# Copy_of_Main.net
KiCad netlist of a schematic drawn in Altium Designer
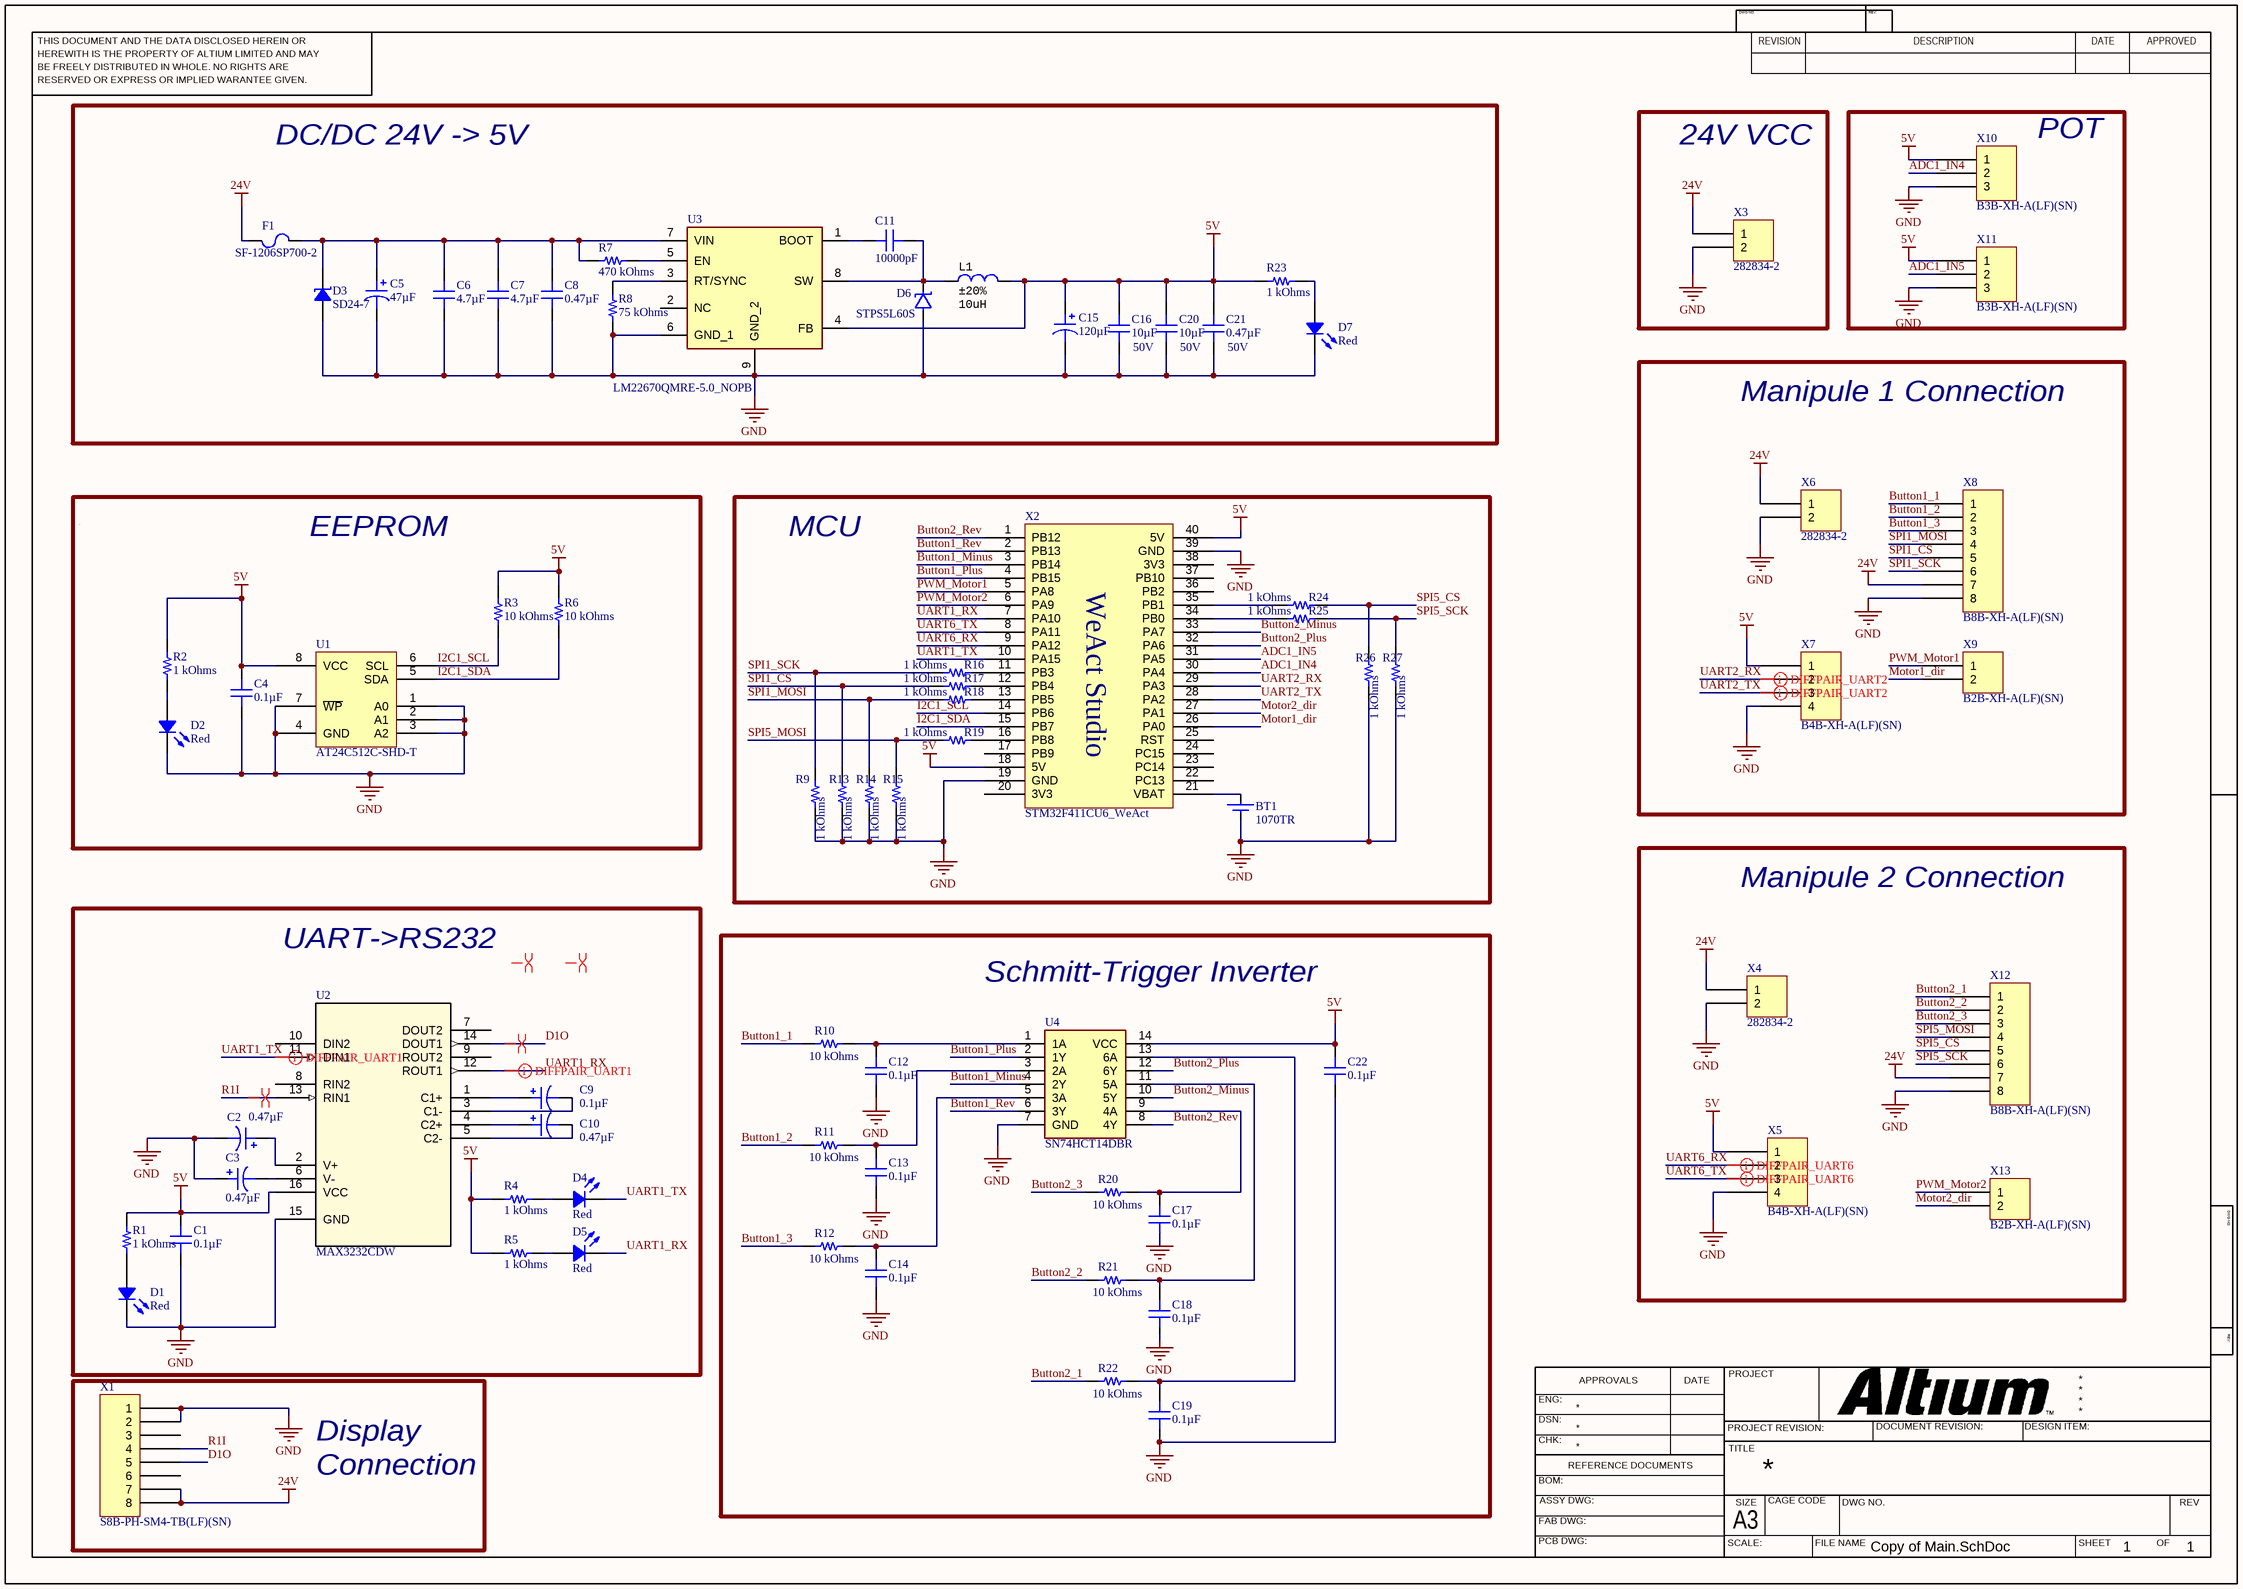
[diagram p0: Copy of Main.SchDoc]

(export (version "E")
  (design (tool "Eeschema 10.0.6"))
  (components
    (comp (ref "BT1")
      (value "1070TR")
      (footprint "SamacSys:1070TR")
      (description "Battery")
      (fields (field (name "MOUSER PART NUMBER") "534-1070TR"))
      (libsource (lib "SamacSys") (part "1070TR"))
    )
    (comp (ref "C1")
      (value "0.1µF")
      (footprint "CAP 0805_2012")
      (description "SMD AUTO X7R, CERAMIC, 0.1 UF, 1")
      (fields (field (name "PART NUMBER") "C0805C104K9RACAUTO") (field (name "MANUFACTURER") "KEMET"))
      (libsource (lib "Celestial Altium Library - altium_library") (part "Capacitor"))
    )
    (comp (ref "C2")
      (value "0.47µF")
      (footprint "CAP POL 1206_3216")
      (description "CAP TANT 0.47UF 10% 35V 1206")
      (fields (field (name "PART NUMBER") "293D474X9035A2TE3") (field (name "MANUFACTURER") "Vishay Sprague"))
      (libsource (lib "Celestial Altium Library - altium_library") (part "Polarised Capacitor"))
    )
    (comp (ref "C3")
      (value "0.47µF")
      (footprint "CAP POL 1206_3216")
      (description "CAP TANT 0.47UF 10% 35V 1206")
      (fields (field (name "PART NUMBER") "293D474X9035A2TE3") (field (name "MANUFACTURER") "Vishay Sprague"))
      (libsource (lib "Celestial Altium Library - altium_library") (part "Polarised Capacitor"))
    )
    (comp (ref "C4")
      (value "0.1µF")
      (footprint "CAP 0805_2012")
      (description "SMD AUTO X7R, CERAMIC, 0.1 UF, 1")
      (fields (field (name "PART NUMBER") "C0805C104K9RACAUTO") (field (name "MANUFACTURER") "KEMET"))
      (libsource (lib "Celestial Altium Library - altium_library") (part "Capacitor"))
    )
    (comp (ref "C5")
      (value "47µF")
      (footprint "CAP ALSMD 8.3MM H10.5MM")
      (description "CAP ALUM 47UF 20% 50V SMD")
      (fields (field (name "PART NUMBER") "UCZ1H470MCL1GS") (field (name "MANUFACTURER") "Nichicon"))
      (libsource (lib "") (part "Polarised Capacitor_1"))
    )
    (comp (ref "C6")
      (value "4.7µF")
      (footprint "CAP 1206_3216 - 1.0MM")
      (description "CAP CER 4.7UF 50V X5R 1206")
      (fields (field (name "PART NUMBER") "UMK316ABJ475KD-T") (field (name "MANUFACTURER") "Taiyo Yuden"))
      (libsource (lib "Celestial Altium Library - altium_library") (part "Capacitor"))
    )
    (comp (ref "C7")
      (value "4.7µF")
      (footprint "CAP 1206_3216 - 1.0MM")
      (description "CAP CER 4.7UF 50V X5R 1206")
      (fields (field (name "PART NUMBER") "UMK316ABJ475KD-T") (field (name "MANUFACTURER") "Taiyo Yuden"))
      (libsource (lib "Celestial Altium Library - altium_library") (part "Capacitor"))
    )
    (comp (ref "C8")
      (value "0.47µF")
      (footprint "CAP 1206_3216 - 1.8MM")
      (description "CAP CER 0.47UF 50V X7R 1206")
      (fields (field (name "PART NUMBER") "AC1206KKX7R9BB474") (field (name "MANUFACTURER") "Yageo"))
      (libsource (lib "Celestial Altium Library - altium_library") (part "Capacitor"))
    )
    (comp (ref "C9")
      (value "0.1µF")
      (footprint "CAP POL 1206_3216")
      (description "CAP TANT 0.1UF 20% 35V 1206")
      (fields (field (name "PART NUMBER") "293D104X0035A2TE3") (field (name "MANUFACTURER") "Vishay Sprague"))
      (libsource (lib "Celestial Altium Library - altium_library") (part "Polarised Capacitor"))
    )
    (comp (ref "C10")
      (value "0.47µF")
      (footprint "CAP POL 1206_3216")
      (description "CAP TANT 0.47UF 10% 35V 1206")
      (fields (field (name "PART NUMBER") "293D474X9035A2TE3") (field (name "MANUFACTURER") "Vishay Sprague"))
      (libsource (lib "Celestial Altium Library - altium_library") (part "Polarised Capacitor"))
    )
    (comp (ref "C11")
      (value "10000pF")
      (footprint "CAP 0805_2012")
      (description "CAP CER SMD 0805 .01UF 6.3V 10%")
      (fields (field (name "PART NUMBER") "C0805Y103K9RAC7800") (field (name "MANUFACTURER") "KEMET"))
      (libsource (lib "Celestial Altium Library - altium_library") (part "Capacitor"))
    )
    (comp (ref "C12")
      (value "0.1µF")
      (footprint "CAP 0805_2012")
      (description "SMD AUTO X7R, CERAMIC, 0.1 UF, 1")
      (fields (field (name "PART NUMBER") "C0805C104K9RACAUTO") (field (name "MANUFACTURER") "KEMET"))
      (libsource (lib "Celestial Altium Library - altium_library") (part "Capacitor"))
    )
    (comp (ref "C13")
      (value "0.1µF")
      (footprint "CAP 0805_2012")
      (description "SMD AUTO X7R, CERAMIC, 0.1 UF, 1")
      (fields (field (name "PART NUMBER") "C0805C104K9RACAUTO") (field (name "MANUFACTURER") "KEMET"))
      (libsource (lib "Celestial Altium Library - altium_library") (part "Capacitor"))
    )
    (comp (ref "C14")
      (value "0.1µF")
      (footprint "CAP 0805_2012")
      (description "SMD AUTO X7R, CERAMIC, 0.1 UF, 1")
      (fields (field (name "PART NUMBER") "C0805C104K9RACAUTO") (field (name "MANUFACTURER") "KEMET"))
      (libsource (lib "Celestial Altium Library - altium_library") (part "Capacitor"))
    )
    (comp (ref "C15")
      (value "120µF")
      (footprint "CAP ALSMD POLY 5.3MM H5.7MM")
      (description "CAP ALUM POLY 120UF 20% 6.3V SMD")
      (fields (field (name "PART NUMBER") "RFS0J121MCN1GS") (field (name "MANUFACTURER") "Nichicon"))
      (libsource (lib "") (part "Polarised Capacitor_1"))
    )
    (comp (ref "C16")
      (value "10µF")
      (footprint "CAP 0805_2012")
      (description "0805 (2012MM) X5R (EIA) 50VDC 10")
      (fields
        (field (name "PART NUMBER") "GRM21BR61H106KE43L")
        (field (name "MANUFACTURER") "Murata Electronics")
        (field (name "VOLTAGE - RATED") "50V")
      )
      (libsource (lib "Celestial Altium Library - altium_library") (part "Capacitor"))
    )
    (comp (ref "C17")
      (value "0.1µF")
      (footprint "CAP 0805_2012")
      (description "SMD AUTO X7R, CERAMIC, 0.1 UF, 1")
      (fields (field (name "PART NUMBER") "C0805C104K9RACAUTO") (field (name "MANUFACTURER") "KEMET"))
      (libsource (lib "Celestial Altium Library - altium_library") (part "Capacitor"))
    )
    (comp (ref "C18")
      (value "0.1µF")
      (footprint "CAP 0805_2012")
      (description "SMD AUTO X7R, CERAMIC, 0.1 UF, 1")
      (fields (field (name "PART NUMBER") "C0805C104K9RACAUTO") (field (name "MANUFACTURER") "KEMET"))
      (libsource (lib "Celestial Altium Library - altium_library") (part "Capacitor"))
    )
    (comp (ref "C19")
      (value "0.1µF")
      (footprint "CAP 0805_2012")
      (description "SMD AUTO X7R, CERAMIC, 0.1 UF, 1")
      (fields (field (name "PART NUMBER") "C0805C104K9RACAUTO") (field (name "MANUFACTURER") "KEMET"))
      (libsource (lib "Celestial Altium Library - altium_library") (part "Capacitor"))
    )
    (comp (ref "C20")
      (value "10µF")
      (footprint "CAP 0805_2012")
      (description "0805 (2012MM) X5R (EIA) 50VDC 10")
      (fields
        (field (name "PART NUMBER") "GRM21BR61H106KE43L")
        (field (name "MANUFACTURER") "Murata Electronics")
        (field (name "VOLTAGE - RATED") "50V")
      )
      (libsource (lib "Celestial Altium Library - altium_library") (part "Capacitor"))
    )
    (comp (ref "C21")
      (value "0.47µF")
      (footprint "CAP 0805_2012")
      (description "CAP CER 0.47UF 50V X7R 0805")
      (fields
        (field (name "PART NUMBER") "GCM21BR71H474KA55L")
        (field (name "MANUFACTURER") "Murata Electronics")
        (field (name "VOLTAGE - RATED") "50V")
      )
      (libsource (lib "Celestial Altium Library - altium_library") (part "Capacitor"))
    )
    (comp (ref "C22")
      (value "0.1µF")
      (footprint "CAP 0805_2012")
      (description "SMD AUTO X7R, CERAMIC, 0.1 UF, 1")
      (fields (field (name "PART NUMBER") "C0805C104K9RACAUTO") (field (name "MANUFACTURER") "KEMET"))
      (libsource (lib "Celestial Altium Library - altium_library") (part "Capacitor"))
    )
    (comp (ref "D1")
      (value "Red")
      (footprint "LED 0603_1608 RED")
      (description "LED RED CLEAR 2SMD")
      (fields
        (field (name "PART NUMBER") "19-213USRC/S259/TR8")
        (field (name "MANUFACTURER") "Everlight Electronics Co Ltd")
      )
      (libsource (lib "Celestial Altium Library - altium_library") (part "LED"))
    )
    (comp (ref "D2")
      (value "Red")
      (footprint "LED 0603_1608 RED")
      (description "LED RED CLEAR 2SMD")
      (fields
        (field (name "PART NUMBER") "19-213USRC/S259/TR8")
        (field (name "MANUFACTURER") "Everlight Electronics Co Ltd")
      )
      (libsource (lib "Celestial Altium Library - altium_library") (part "LED"))
    )
    (comp (ref "D3")
      (value "SD24-7")
      (footprint "SOD323")
      (description "SURGE PROTECTION PP SOD323")
      (fields (field (name "MANUFACTURER") "Diodes Incorporated"))
      (libsource (lib "Celestial Altium Library - altium_library") (part "DIODE TVS UNI"))
    )
    (comp (ref "D4")
      (value "Red")
      (footprint "LED 0603_1608 RED")
      (description "LED RED CLEAR 2SMD")
      (fields
        (field (name "PART NUMBER") "19-213USRC/S259/TR8")
        (field (name "MANUFACTURER") "Everlight Electronics Co Ltd")
      )
      (libsource (lib "Celestial Altium Library - altium_library") (part "LED"))
    )
    (comp (ref "D5")
      (value "Red")
      (footprint "LED 0603_1608 RED")
      (description "LED RED CLEAR 2SMD")
      (fields
        (field (name "PART NUMBER") "19-213USRC/S259/TR8")
        (field (name "MANUFACTURER") "Everlight Electronics Co Ltd")
      )
      (libsource (lib "Celestial Altium Library - altium_library") (part "LED"))
    )
    (comp (ref "D6")
      (value "STPS5L60S")
      (footprint "SamacSys:DIOM8059X265N")
      (description "DIODE SCHOTTKY 60V 5A SMC")
      (fields (field (name "MOUSER PART NUMBER") "511-STPS5L60S"))
      (libsource (lib "SamacSys") (part "STPS5L60S"))
    )
    (comp (ref "D7")
      (value "Red")
      (footprint "LED 0603_1608 RED")
      (description "LED RED CLEAR 2SMD")
      (fields
        (field (name "PART NUMBER") "19-213USRC/S259/TR8")
        (field (name "MANUFACTURER") "Everlight Electronics Co Ltd")
      )
      (libsource (lib "Celestial Altium Library - altium_library") (part "LED"))
    )
    (comp (ref "F1")
      (value "SF-1206SP700-2")
      (footprint "FUSE 1206_3216 0.6MM")
      (description "FUSE BOARD MOUNT 7A 32VDC 1206")
      (fields (field (name "MANUFACTURER") "Bourns Inc."))
      (libsource (lib "Celestial Altium Library - altium_library") (part "MOUNTED FUSE"))
    )
    (comp (ref "L1")
      (value "10uH")
      (footprint "IND: SRP7028A")
      (fields
        (field (name "MANUFACTURER") "Bourns Inc.")
        (field (name "PARTNUMBER") "SRP7028A-100M")
        (field (name "VALUEMANUFACTURERPARTNUMBER") "Fixed inductor, 10uH, ±20%, SRP7028A, 3.5A, -40...+150°C")
        (field (name "TOLERANCE") "±20%")
      )
      (libsource (lib "inductor") (part "Inductor_SMD"))
    )
    (comp (ref "R1")
      (value "1 kOhms")
      (footprint "RES 0805_2012")
      (description "RES SMD 1K OHM 0.1% 1/8W 0805")
      (fields (field (name "PART NUMBER") "RT0805BRE071KL") (field (name "MANUFACTURER") "Yageo"))
      (libsource (lib "Celestial Altium Library - altium_library") (part "Resistor"))
    )
    (comp (ref "R2")
      (value "1 kOhms")
      (footprint "RES 0805_2012")
      (description "RES SMD 1K OHM 0.1% 1/8W 0805")
      (fields (field (name "PART NUMBER") "RT0805BRE071KL") (field (name "MANUFACTURER") "Yageo"))
      (libsource (lib "Celestial Altium Library - altium_library") (part "Resistor"))
    )
    (comp (ref "R3")
      (value "10 kOhms")
      (footprint "RES 0805_2012")
      (description "RES SMD 10K OHM 0.5% 1/8W 0805")
      (fields (field (name "PART NUMBER") "RT0805DRD0710KL") (field (name "MANUFACTURER") "Yageo"))
      (libsource (lib "Celestial Altium Library - altium_library") (part "Resistor"))
    )
    (comp (ref "R4")
      (value "1 kOhms")
      (footprint "RES 0805_2012")
      (description "RES SMD 1K OHM 0.1% 1/8W 0805")
      (fields (field (name "PART NUMBER") "RT0805BRE071KL") (field (name "MANUFACTURER") "Yageo"))
      (libsource (lib "Celestial Altium Library - altium_library") (part "Resistor"))
    )
    (comp (ref "R5")
      (value "1 kOhms")
      (footprint "RES 0805_2012")
      (description "RES SMD 1K OHM 0.1% 1/8W 0805")
      (fields (field (name "PART NUMBER") "RT0805BRE071KL") (field (name "MANUFACTURER") "Yageo"))
      (libsource (lib "Celestial Altium Library - altium_library") (part "Resistor"))
    )
    (comp (ref "R6")
      (value "10 kOhms")
      (footprint "RES 0805_2012")
      (description "RES SMD 10K OHM 0.5% 1/8W 0805")
      (fields (field (name "PART NUMBER") "RT0805DRD0710KL") (field (name "MANUFACTURER") "Yageo"))
      (libsource (lib "Celestial Altium Library - altium_library") (part "Resistor"))
    )
    (comp (ref "R7")
      (value "470 kOhms")
      (footprint "RES 0805_2012")
      (description "RES SMD 470K OHM 5% 1/8W 0805")
      (fields (field (name "PART NUMBER") "CR0805-JW-474ELF") (field (name "MANUFACTURER") "Bourns Inc."))
      (libsource (lib "Celestial Altium Library - altium_library") (part "Resistor"))
    )
    (comp (ref "R8")
      (value "75 kOhms")
      (footprint "RES 0805_2012")
      (description "RES SMD 75K OHM 1% 1/8W 0805")
      (fields
        (field (name "PART NUMBER") "ERJ-6ENF7502V")
        (field (name "MANUFACTURER") "Panasonic Electronic Components")
      )
      (libsource (lib "Celestial Altium Library - altium_library") (part "Resistor"))
    )
    (comp (ref "R9")
      (value "1 kOhms")
      (footprint "RES 0805_2012")
      (description "RES SMD 1K OHM 0.1% 1/8W 0805")
      (fields (field (name "PART NUMBER") "RT0805BRE071KL") (field (name "MANUFACTURER") "Yageo"))
      (libsource (lib "Celestial Altium Library - altium_library") (part "Resistor"))
    )
    (comp (ref "R10")
      (value "10 kOhms")
      (footprint "RES 0805_2012")
      (description "RES SMD 10K OHM 0.5% 1/8W 0805")
      (fields (field (name "PART NUMBER") "RT0805DRD0710KL") (field (name "MANUFACTURER") "Yageo"))
      (libsource (lib "Celestial Altium Library - altium_library") (part "Resistor"))
    )
    (comp (ref "R11")
      (value "10 kOhms")
      (footprint "RES 0805_2012")
      (description "RES SMD 10K OHM 0.5% 1/8W 0805")
      (fields (field (name "PART NUMBER") "RT0805DRD0710KL") (field (name "MANUFACTURER") "Yageo"))
      (libsource (lib "Celestial Altium Library - altium_library") (part "Resistor"))
    )
    (comp (ref "R12")
      (value "10 kOhms")
      (footprint "RES 0805_2012")
      (description "RES SMD 10K OHM 0.5% 1/8W 0805")
      (fields (field (name "PART NUMBER") "RT0805DRD0710KL") (field (name "MANUFACTURER") "Yageo"))
      (libsource (lib "Celestial Altium Library - altium_library") (part "Resistor"))
    )
    (comp (ref "R13")
      (value "1 kOhms")
      (footprint "RES 0805_2012")
      (description "RES SMD 1K OHM 0.1% 1/8W 0805")
      (fields (field (name "PART NUMBER") "RT0805BRE071KL") (field (name "MANUFACTURER") "Yageo"))
      (libsource (lib "Celestial Altium Library - altium_library") (part "Resistor"))
    )
    (comp (ref "R14")
      (value "1 kOhms")
      (footprint "RES 0805_2012")
      (description "RES SMD 1K OHM 0.1% 1/8W 0805")
      (fields (field (name "PART NUMBER") "RT0805BRE071KL") (field (name "MANUFACTURER") "Yageo"))
      (libsource (lib "Celestial Altium Library - altium_library") (part "Resistor"))
    )
    (comp (ref "R15")
      (value "1 kOhms")
      (footprint "RES 0805_2012")
      (description "RES SMD 1K OHM 0.1% 1/8W 0805")
      (fields (field (name "PART NUMBER") "RT0805BRE071KL") (field (name "MANUFACTURER") "Yageo"))
      (libsource (lib "Celestial Altium Library - altium_library") (part "Resistor"))
    )
    (comp (ref "R16")
      (value "1 kOhms")
      (footprint "RES 0805_2012")
      (description "RES SMD 1K OHM 0.1% 1/8W 0805")
      (fields (field (name "PART NUMBER") "RT0805BRE071KL") (field (name "MANUFACTURER") "Yageo"))
      (libsource (lib "Celestial Altium Library - altium_library") (part "Resistor"))
    )
    (comp (ref "R17")
      (value "1 kOhms")
      (footprint "RES 0805_2012")
      (description "RES SMD 1K OHM 0.1% 1/8W 0805")
      (fields (field (name "PART NUMBER") "RT0805BRE071KL") (field (name "MANUFACTURER") "Yageo"))
      (libsource (lib "Celestial Altium Library - altium_library") (part "Resistor"))
    )
    (comp (ref "R18")
      (value "1 kOhms")
      (footprint "RES 0805_2012")
      (description "RES SMD 1K OHM 0.1% 1/8W 0805")
      (fields (field (name "PART NUMBER") "RT0805BRE071KL") (field (name "MANUFACTURER") "Yageo"))
      (libsource (lib "Celestial Altium Library - altium_library") (part "Resistor"))
    )
    (comp (ref "R19")
      (value "1 kOhms")
      (footprint "RES 0805_2012")
      (description "RES SMD 1K OHM 0.1% 1/8W 0805")
      (fields (field (name "PART NUMBER") "RT0805BRE071KL") (field (name "MANUFACTURER") "Yageo"))
      (libsource (lib "Celestial Altium Library - altium_library") (part "Resistor"))
    )
    (comp (ref "R20")
      (value "10 kOhms")
      (footprint "RES 0805_2012")
      (description "RES SMD 10K OHM 0.5% 1/8W 0805")
      (fields (field (name "PART NUMBER") "RT0805DRD0710KL") (field (name "MANUFACTURER") "Yageo"))
      (libsource (lib "Celestial Altium Library - altium_library") (part "Resistor"))
    )
    (comp (ref "R21")
      (value "10 kOhms")
      (footprint "RES 0805_2012")
      (description "RES SMD 10K OHM 0.5% 1/8W 0805")
      (fields (field (name "PART NUMBER") "RT0805DRD0710KL") (field (name "MANUFACTURER") "Yageo"))
      (libsource (lib "Celestial Altium Library - altium_library") (part "Resistor"))
    )
    (comp (ref "R22")
      (value "10 kOhms")
      (footprint "RES 0805_2012")
      (description "RES SMD 10K OHM 0.5% 1/8W 0805")
      (fields (field (name "PART NUMBER") "RT0805DRD0710KL") (field (name "MANUFACTURER") "Yageo"))
      (libsource (lib "Celestial Altium Library - altium_library") (part "Resistor"))
    )
    (comp (ref "R23")
      (value "1 kOhms")
      (footprint "RES 0805_2012")
      (description "RES SMD 1K OHM 0.1% 1/8W 0805")
      (fields (field (name "PART NUMBER") "RT0805BRE071KL") (field (name "MANUFACTURER") "Yageo"))
      (libsource (lib "Celestial Altium Library - altium_library") (part "Resistor"))
    )
    (comp (ref "R24")
      (value "1 kOhms")
      (footprint "RES 0805_2012")
      (description "RES SMD 1K OHM 0.1% 1/8W 0805")
      (fields (field (name "PART NUMBER") "RT0805BRE071KL") (field (name "MANUFACTURER") "Yageo"))
      (libsource (lib "Celestial Altium Library - altium_library") (part "Resistor"))
    )
    (comp (ref "R25")
      (value "1 kOhms")
      (footprint "RES 0805_2012")
      (description "RES SMD 1K OHM 0.1% 1/8W 0805")
      (fields (field (name "PART NUMBER") "RT0805BRE071KL") (field (name "MANUFACTURER") "Yageo"))
      (libsource (lib "Celestial Altium Library - altium_library") (part "Resistor"))
    )
    (comp (ref "R26")
      (value "1 kOhms")
      (footprint "RES 0805_2012")
      (description "RES SMD 1K OHM 0.1% 1/8W 0805")
      (fields (field (name "PART NUMBER") "RT0805BRE071KL") (field (name "MANUFACTURER") "Yageo"))
      (libsource (lib "Celestial Altium Library - altium_library") (part "Resistor"))
    )
    (comp (ref "R27")
      (value "1 kOhms")
      (footprint "RES 0805_2012")
      (description "RES SMD 1K OHM 0.1% 1/8W 0805")
      (fields (field (name "PART NUMBER") "RT0805BRE071KL") (field (name "MANUFACTURER") "Yageo"))
      (libsource (lib "Celestial Altium Library - altium_library") (part "Resistor"))
    )
    (comp (ref "U1")
      (value "AT24C512C-SHD-T")
      (footprint "MICROCHIP SOIC-8 208MIL WIDE")
      (description "IC EEPROM 512K I2C 1MHZ 8SOIC")
      (fields (field (name "MANUFACTURER") "Microchip Technology"))
      (libsource (lib "Celestial Altium Library - altium_library") (part "MICROCHIP EEPROM I2C 8PIN"))
    )
    (comp (ref "U2")
      (value "MAX3232CDW")
      (footprint "DW16")
      (description "No Description Available")
      (fields (field (name "COPYRIGHT") "Copyright (C) 2022 Ultra Librarian. All rights reserved."))
      (libsource (lib "MAX3232CDW") (part "MAX3232CDW"))
    )
    (comp (ref "U3")
      (value "LM22670QMRE-5.0_NOPB")
      (footprint "SamacSys:SOIC127P600X170-9N")
      (description "Buck Switching Regulator IC Positive Fixed 5V 1 Output 3A 8-PowerSOIC (0.154\", 3.90mm Width)")
      (fields
        (field (name "MANUFACTURER_PART_NUMBER") "LM22670QMRE-5.0/NOPB")
        (field (name "MOUSER PART NUMBER") "926-LM22670QMRE50NPB")
      )
      (libsource (lib "SamacSys") (part "LM22670QMRE-5.0_NOPB"))
    )
    (comp (ref "U4")
      (value "SN74HCT14DBR")
      (footprint "SamacSys:SOP65P780X200-14N")
      (description "Integrated Circuit")
      (fields (field (name "MOUSER PART NUMBER") "595-SN74HCT14DBR"))
      (libsource (lib "*") (part "SN74HCT14DBR"))
    )
    (comp (ref "X1")
      (value "S8B-PH-SM4-TB(LF)(SN)")
      (footprint "JST S8B-PH-SM4-TB")
      (description "CONN HEADER SMD R/A 8POS 2MM")
      (fields (field (name "MANUFACTURER") "JST Sales America Inc."))
      (libsource (lib "Celestial Altium Library - altium_library") (part "8 Pin"))
    )
    (comp (ref "X2")
      (value "STM32F411CU6_WeAct")
      (footprint "STM32F4x1CxU6 WeActStudio")
      (libsource (lib "Lib_Massage") (part "STM32F411CU6_WeAct"))
    )
    (comp (ref "X3")
      (value "282834-2")
      (footprint "TE 282834-2")
      (description "TERM BLK 2P SIDE ENT 2.54MM PCB")
      (fields (field (name "MANUFACTURER") "TE Connectivity AMP Connectors") (field (name "VOLTAGE") "150V"))
      (libsource (lib "Celestial Altium Library - altium_library") (part "2 Pin"))
    )
    (comp (ref "X4")
      (value "282834-2")
      (footprint "TE 282834-2")
      (description "TERM BLK 2P SIDE ENT 2.54MM PCB")
      (fields (field (name "MANUFACTURER") "TE Connectivity AMP Connectors") (field (name "VOLTAGE") "150V"))
      (libsource (lib "Celestial Altium Library - altium_library") (part "2 Pin"))
    )
    (comp (ref "X5")
      (value "B4B-XH-A(LF)(SN)")
      (footprint "JST XH B4B-XH-A")
      (description "CONN HEADER VERT 4POS 2.5MM")
      (fields (field (name "MANUFACTURER") "JST Sales America Inc."))
      (libsource (lib "Celestial Altium Library - altium_library") (part "4 Pin"))
    )
    (comp (ref "X6")
      (value "282834-2")
      (footprint "TE 282834-2")
      (description "TERM BLK 2P SIDE ENT 2.54MM PCB")
      (fields (field (name "MANUFACTURER") "TE Connectivity AMP Connectors") (field (name "VOLTAGE") "150V"))
      (libsource (lib "Celestial Altium Library - altium_library") (part "2 Pin"))
    )
    (comp (ref "X7")
      (value "B4B-XH-A(LF)(SN)")
      (footprint "JST XH B4B-XH-A")
      (description "CONN HEADER VERT 4POS 2.5MM")
      (fields (field (name "MANUFACTURER") "JST Sales America Inc."))
      (libsource (lib "Celestial Altium Library - altium_library") (part "4 Pin"))
    )
    (comp (ref "X8")
      (value "B8B-XH-A(LF)(SN)")
      (footprint "JST XH B8B-XH-A")
      (description "CONN HEADER VERT 8POS 2.5MM")
      (fields (field (name "MANUFACTURER") "JST Sales America Inc."))
      (libsource (lib "") (part "8 Pin_1"))
    )
    (comp (ref "X9")
      (value "B2B-XH-A(LF)(SN)")
      (footprint "JST XH B2B-XH-A")
      (description "CONN HEADER VERT 2POS 2.5MM")
      (fields (field (name "MANUFACTURER") "JST Sales America Inc."))
      (libsource (lib "Celestial Altium Library - altium_library") (part "2 Pin"))
    )
    (comp (ref "X10")
      (value "B3B-XH-A(LF)(SN)")
      (footprint "JST XH B3B-XH-A")
      (description "CONN HEADER VERT 3POS 2.5MM")
      (fields (field (name "MANUFACTURER") "JST Sales America Inc."))
      (libsource (lib "Celestial Altium Library - altium_library") (part "3 Pin"))
    )
    (comp (ref "X11")
      (value "B3B-XH-A(LF)(SN)")
      (footprint "JST XH B3B-XH-A")
      (description "CONN HEADER VERT 3POS 2.5MM")
      (fields (field (name "MANUFACTURER") "JST Sales America Inc."))
      (libsource (lib "Celestial Altium Library - altium_library") (part "3 Pin"))
    )
    (comp (ref "X12")
      (value "B8B-XH-A(LF)(SN)")
      (footprint "JST XH B8B-XH-A")
      (description "CONN HEADER VERT 8POS 2.5MM")
      (fields (field (name "MANUFACTURER") "JST Sales America Inc."))
      (libsource (lib "") (part "8 Pin_1"))
    )
    (comp (ref "X13")
      (value "B2B-XH-A(LF)(SN)")
      (footprint "JST XH B2B-XH-A")
      (description "CONN HEADER VERT 2POS 2.5MM")
      (fields (field (name "MANUFACTURER") "JST Sales America Inc."))
      (libsource (lib "Celestial Altium Library - altium_library") (part "2 Pin"))
    )
  )
  (nets
    (net (code "1") (name "/ADC1_IN4") (class "Default")
      (node (ref "X10") (pin "2") (pinfunction "2_2") (pintype "passive"))
      (node (ref "X2") (pin "30") (pinfunction "PA4_30") (pintype "passive"))
    )
    (net (code "2") (name "/ADC1_IN5") (class "Default")
      (node (ref "X11") (pin "2") (pinfunction "2_2") (pintype "passive"))
      (node (ref "X2") (pin "31") (pinfunction "PA5_31") (pintype "passive"))
    )
    (net (code "3") (name "/Button1_1") (class "Default")
      (node (ref "R10") (pin "2") (pinfunction "2_2") (pintype "passive"))
      (node (ref "X8") (pin "1") (pinfunction "1_1") (pintype "passive"))
    )
    (net (code "4") (name "/Button1_2") (class "Default")
      (node (ref "R11") (pin "2") (pinfunction "2_2") (pintype "passive"))
      (node (ref "X8") (pin "2") (pinfunction "2_2") (pintype "passive"))
    )
    (net (code "5") (name "/Button1_3") (class "Default")
      (node (ref "R12") (pin "2") (pinfunction "2_2") (pintype "passive"))
      (node (ref "X8") (pin "3") (pinfunction "3_3") (pintype "passive"))
    )
    (net (code "6") (name "/Button1_Minus") (class "Default")
      (node (ref "U4") (pin "4") (pinfunction "2Y_4") (pintype "passive"))
      (node (ref "X2") (pin "3") (pinfunction "PB14_3") (pintype "passive"))
    )
    (net (code "7") (name "/Button1_Plus") (class "Default")
      (node (ref "U4") (pin "2") (pinfunction "1Y_2") (pintype "passive"))
      (node (ref "X2") (pin "4") (pinfunction "PB15_4") (pintype "passive"))
    )
    (net (code "8") (name "/Button1_Rev") (class "Default")
      (node (ref "U4") (pin "6") (pinfunction "3Y_6") (pintype "passive"))
      (node (ref "X2") (pin "2") (pinfunction "PB13_2") (pintype "passive"))
    )
    (net (code "9") (name "/Button2_1") (class "Default")
      (node (ref "R22") (pin "2") (pinfunction "2_2") (pintype "passive"))
      (node (ref "X12") (pin "1") (pinfunction "1_1") (pintype "passive"))
    )
    (net (code "10") (name "/Button2_2") (class "Default")
      (node (ref "R21") (pin "2") (pinfunction "2_2") (pintype "passive"))
      (node (ref "X12") (pin "2") (pinfunction "2_2") (pintype "passive"))
    )
    (net (code "11") (name "/Button2_3") (class "Default")
      (node (ref "R20") (pin "2") (pinfunction "2_2") (pintype "passive"))
      (node (ref "X12") (pin "3") (pinfunction "3_3") (pintype "passive"))
    )
    (net (code "12") (name "/Button2_Minus") (class "Default")
      (node (ref "U4") (pin "10") (pinfunction "5Y_10") (pintype "passive"))
      (node (ref "X2") (pin "33") (pinfunction "PA7_33") (pintype "passive"))
    )
    (net (code "13") (name "/Button2_Plus") (class "Default")
      (node (ref "U4") (pin "12") (pinfunction "6Y_12") (pintype "passive"))
      (node (ref "X2") (pin "32") (pinfunction "PA6_32") (pintype "passive"))
    )
    (net (code "14") (name "/Button2_Rev") (class "Default")
      (node (ref "U4") (pin "8") (pinfunction "4Y_8") (pintype "passive"))
      (node (ref "X2") (pin "1") (pinfunction "PB12_1") (pintype "passive"))
    )
    (net (code "15") (name "/D1O") (class "Default")
      (node (ref "U2") (pin "14") (pinfunction "DOUT1_14") (pintype "output"))
      (node (ref "X1") (pin "5") (pinfunction "5_5") (pintype "passive"))
    )
    (net (code "16") (name "/I2C1_SCL") (class "Default")
      (node (ref "R3") (pin "1") (pinfunction "1_1") (pintype "passive"))
      (node (ref "U1") (pin "6") (pinfunction "SCL_6") (pintype "passive"))
      (node (ref "X2") (pin "14") (pinfunction "PB6_14") (pintype "passive"))
    )
    (net (code "17") (name "/I2C1_SDA") (class "Default")
      (node (ref "R6") (pin "1") (pinfunction "1_1") (pintype "passive"))
      (node (ref "U1") (pin "5") (pinfunction "SDA_5") (pintype "passive"))
      (node (ref "X2") (pin "15") (pinfunction "PB7_15") (pintype "passive"))
    )
    (net (code "18") (name "/Motor1_dir") (class "Default")
      (node (ref "X2") (pin "26") (pinfunction "PA0_26") (pintype "passive"))
      (node (ref "X9") (pin "2") (pinfunction "2_2") (pintype "passive"))
    )
    (net (code "19") (name "/Motor2_dir") (class "Default")
      (node (ref "X13") (pin "2") (pinfunction "2_2") (pintype "passive"))
      (node (ref "X2") (pin "27") (pinfunction "PA1_27") (pintype "passive"))
    )
    (net (code "20") (name "/PWM_Motor1") (class "Default")
      (node (ref "X2") (pin "5") (pinfunction "PA8_5") (pintype "passive"))
      (node (ref "X9") (pin "1") (pinfunction "1_1") (pintype "passive"))
    )
    (net (code "21") (name "/PWM_Motor2") (class "Default")
      (node (ref "X13") (pin "1") (pinfunction "1_1") (pintype "passive"))
      (node (ref "X2") (pin "6") (pinfunction "PA9_6") (pintype "passive"))
    )
    (net (code "22") (name "/R1I") (class "Default")
      (node (ref "U2") (pin "13") (pinfunction "RIN1_13") (pintype "input"))
      (node (ref "X1") (pin "4") (pinfunction "4_4") (pintype "passive"))
    )
    (net (code "23") (name "/SPI1_CS") (class "Default")
      (node (ref "R13") (pin "1") (pinfunction "1_1") (pintype "passive"))
      (node (ref "R17") (pin "2") (pinfunction "2_2") (pintype "passive"))
      (node (ref "X8") (pin "5") (pinfunction "5_5") (pintype "passive"))
    )
    (net (code "24") (name "/SPI1_MOSI") (class "Default")
      (node (ref "R14") (pin "1") (pinfunction "1_1") (pintype "passive"))
      (node (ref "R18") (pin "2") (pinfunction "2_2") (pintype "passive"))
      (node (ref "X8") (pin "4") (pinfunction "4_4") (pintype "passive"))
    )
    (net (code "25") (name "/SPI1_SCK") (class "Default")
      (node (ref "R16") (pin "2") (pinfunction "2_2") (pintype "passive"))
      (node (ref "R9") (pin "1") (pinfunction "1_1") (pintype "passive"))
      (node (ref "X8") (pin "6") (pinfunction "6_6") (pintype "passive"))
    )
    (net (code "26") (name "/SPI5_CS") (class "Default")
      (node (ref "R24") (pin "1") (pinfunction "1_1") (pintype "passive"))
      (node (ref "R26") (pin "1") (pinfunction "1_1") (pintype "passive"))
      (node (ref "X12") (pin "5") (pinfunction "5_5") (pintype "passive"))
    )
    (net (code "27") (name "/SPI5_MOSI") (class "Default")
      (node (ref "R15") (pin "1") (pinfunction "1_1") (pintype "passive"))
      (node (ref "R19") (pin "2") (pinfunction "2_2") (pintype "passive"))
      (node (ref "X12") (pin "4") (pinfunction "4_4") (pintype "passive"))
    )
    (net (code "28") (name "/SPI5_SCK") (class "Default")
      (node (ref "R25") (pin "1") (pinfunction "1_1") (pintype "passive"))
      (node (ref "R27") (pin "1") (pinfunction "1_1") (pintype "passive"))
      (node (ref "X12") (pin "6") (pinfunction "6_6") (pintype "passive"))
    )
    (net (code "29") (name "/UART1_RX") (class "Default")
      (node (ref "D5") (pin "2") (pinfunction "2_2") (pintype "passive"))
      (node (ref "U2") (pin "12") (pinfunction "ROUT1_12") (pintype "output"))
      (node (ref "X2") (pin "7") (pinfunction "PA10_7") (pintype "passive"))
    )
    (net (code "30") (name "/UART1_TX") (class "Default")
      (node (ref "D4") (pin "2") (pinfunction "2_2") (pintype "passive"))
      (node (ref "U2") (pin "11") (pinfunction "DIN1_11") (pintype "input"))
      (node (ref "X2") (pin "10") (pinfunction "PA15_10") (pintype "passive"))
    )
    (net (code "31") (name "/UART2_RX") (class "Default")
      (node (ref "X2") (pin "29") (pinfunction "PA3_29") (pintype "passive"))
      (node (ref "X7") (pin "2") (pinfunction "2_2") (pintype "passive"))
    )
    (net (code "32") (name "/UART2_TX") (class "Default")
      (node (ref "X2") (pin "28") (pinfunction "PA2_28") (pintype "passive"))
      (node (ref "X7") (pin "3") (pinfunction "3_3") (pintype "passive"))
    )
    (net (code "33") (name "/UART6_RX") (class "Default")
      (node (ref "X2") (pin "9") (pinfunction "PA12_9") (pintype "passive"))
      (node (ref "X5") (pin "2") (pinfunction "2_2") (pintype "passive"))
    )
    (net (code "34") (name "/UART6_TX") (class "Default")
      (node (ref "X2") (pin "8") (pinfunction "PA11_8") (pintype "passive"))
      (node (ref "X5") (pin "3") (pinfunction "3_3") (pintype "passive"))
    )
    (net (code "35") (name "5V") (class "Default")
      (node (ref "C1") (pin "2") (pinfunction "2_2") (pintype "passive"))
      (node (ref "C15") (pin "1") (pinfunction "1_1") (pintype "passive"))
      (node (ref "C16") (pin "1") (pinfunction "1_1") (pintype "passive"))
      (node (ref "C20") (pin "1") (pinfunction "1_1") (pintype "passive"))
      (node (ref "C21") (pin "2") (pinfunction "2_2") (pintype "passive"))
      (node (ref "C22") (pin "2") (pinfunction "2_2") (pintype "passive"))
      (node (ref "C4") (pin "2") (pinfunction "2_2") (pintype "passive"))
      (node (ref "L1") (pin "1") (pinfunction "1_1") (pintype "passive"))
      (node (ref "R1") (pin "2") (pinfunction "2_2") (pintype "passive"))
      (node (ref "R2") (pin "2") (pinfunction "2_2") (pintype "passive"))
      (node (ref "R23") (pin "2") (pinfunction "2_2") (pintype "passive"))
      (node (ref "R3") (pin "2") (pinfunction "2_2") (pintype "passive"))
      (node (ref "R4") (pin "2") (pinfunction "2_2") (pintype "passive"))
      (node (ref "R5") (pin "2") (pinfunction "2_2") (pintype "passive"))
      (node (ref "R6") (pin "2") (pinfunction "2_2") (pintype "passive"))
      (node (ref "U1") (pin "8") (pinfunction "VCC_8") (pintype "passive"))
      (node (ref "U2") (pin "16") (pinfunction "VCC_16") (pintype "power_in"))
      (node (ref "U3") (pin "4") (pinfunction "FB_4") (pintype "passive"))
      (node (ref "U4") (pin "14") (pinfunction "VCC_14") (pintype "passive"))
      (node (ref "X10") (pin "1") (pinfunction "1_1") (pintype "passive"))
      (node (ref "X11") (pin "1") (pinfunction "1_1") (pintype "passive"))
      (node (ref "X2") (pin "18") (pinfunction "5V_18") (pintype "passive"))
      (node (ref "X2") (pin "40") (pinfunction "5V_40") (pintype "passive"))
      (node (ref "X5") (pin "1") (pinfunction "1_1") (pintype "passive"))
      (node (ref "X7") (pin "1") (pinfunction "1_1") (pintype "passive"))
    )
    (net (code "36") (name "24V") (class "Default")
      (node (ref "F1") (pin "1") (pintype "passive"))
      (node (ref "X1") (pin "7") (pinfunction "7_7") (pintype "passive"))
      (node (ref "X1") (pin "8") (pinfunction "8_8") (pintype "passive"))
      (node (ref "X12") (pin "7") (pinfunction "7_7") (pintype "passive"))
      (node (ref "X3") (pin "1") (pinfunction "1_1") (pintype "passive"))
      (node (ref "X4") (pin "1") (pinfunction "1_1") (pintype "passive"))
      (node (ref "X6") (pin "1") (pinfunction "1_1") (pintype "passive"))
      (node (ref "X8") (pin "7") (pinfunction "7_7") (pintype "passive"))
    )
    (net (code "37") (name "GND") (class "Default")
      (node (ref "BT1") (pin "2") (pinfunction "-_2") (pintype "power_in"))
      (node (ref "C1") (pin "1") (pinfunction "1_1") (pintype "passive"))
      (node (ref "C12") (pin "1") (pinfunction "1_1") (pintype "passive"))
      (node (ref "C13") (pin "1") (pinfunction "1_1") (pintype "passive"))
      (node (ref "C14") (pin "1") (pinfunction "1_1") (pintype "passive"))
      (node (ref "C15") (pin "2") (pinfunction "2_2") (pintype "passive"))
      (node (ref "C16") (pin "2") (pinfunction "2_2") (pintype "passive"))
      (node (ref "C17") (pin "1") (pinfunction "1_1") (pintype "passive"))
      (node (ref "C18") (pin "1") (pinfunction "1_1") (pintype "passive"))
      (node (ref "C19") (pin "1") (pinfunction "1_1") (pintype "passive"))
      (node (ref "C2") (pin "2") (pinfunction "2_2") (pintype "passive"))
      (node (ref "C20") (pin "2") (pinfunction "2_2") (pintype "passive"))
      (node (ref "C21") (pin "1") (pinfunction "1_1") (pintype "passive"))
      (node (ref "C22") (pin "1") (pinfunction "1_1") (pintype "passive"))
      (node (ref "C3") (pin "1") (pinfunction "1_1") (pintype "passive"))
      (node (ref "C4") (pin "1") (pinfunction "1_1") (pintype "passive"))
      (node (ref "C5") (pin "2") (pinfunction "2_2") (pintype "passive"))
      (node (ref "C6") (pin "1") (pinfunction "1_1") (pintype "passive"))
      (node (ref "C7") (pin "1") (pinfunction "1_1") (pintype "passive"))
      (node (ref "C8") (pin "1") (pinfunction "1_1") (pintype "passive"))
      (node (ref "D1") (pin "2") (pinfunction "2_2") (pintype "passive"))
      (node (ref "D2") (pin "2") (pinfunction "2_2") (pintype "passive"))
      (node (ref "D3") (pin "1") (pinfunction "1_1") (pintype "passive"))
      (node (ref "D6") (pin "1") (pinfunction "1_1") (pintype "passive"))
      (node (ref "D7") (pin "2") (pinfunction "2_2") (pintype "passive"))
      (node (ref "R13") (pin "2") (pinfunction "2_2") (pintype "passive"))
      (node (ref "R14") (pin "2") (pinfunction "2_2") (pintype "passive"))
      (node (ref "R15") (pin "2") (pinfunction "2_2") (pintype "passive"))
      (node (ref "R26") (pin "2") (pinfunction "2_2") (pintype "passive"))
      (node (ref "R27") (pin "2") (pinfunction "2_2") (pintype "passive"))
      (node (ref "R8") (pin "1") (pinfunction "1_1") (pintype "passive"))
      (node (ref "R9") (pin "2") (pinfunction "2_2") (pintype "passive"))
      (node (ref "U1") (pin "1") (pinfunction "A0_1") (pintype "passive"))
      (node (ref "U1") (pin "2") (pinfunction "A1_2") (pintype "passive"))
      (node (ref "U1") (pin "3") (pinfunction "A2_3") (pintype "passive"))
      (node (ref "U1") (pin "4") (pinfunction "GND_4") (pintype "passive"))
      (node (ref "U1") (pin "7") (pinfunction "~{WP}_7") (pintype "passive"))
      (node (ref "U2") (pin "15") (pinfunction "GND_15") (pintype "power_in"))
      (node (ref "U3") (pin "6") (pinfunction "GND_1_6") (pintype "passive"))
      (node (ref "U3") (pin "9") (pinfunction "GND_2_9") (pintype "passive"))
      (node (ref "U4") (pin "7") (pinfunction "GND_7") (pintype "passive"))
      (node (ref "X1") (pin "1") (pinfunction "1_1") (pintype "passive"))
      (node (ref "X1") (pin "2") (pinfunction "2_2") (pintype "passive"))
      (node (ref "X10") (pin "3") (pinfunction "3_3") (pintype "passive"))
      (node (ref "X11") (pin "3") (pinfunction "3_3") (pintype "passive"))
      (node (ref "X12") (pin "8") (pinfunction "8_8") (pintype "passive"))
      (node (ref "X2") (pin "19") (pinfunction "GND_19") (pintype "passive"))
      (node (ref "X2") (pin "39") (pinfunction "GND_39") (pintype "passive"))
      (node (ref "X3") (pin "2") (pinfunction "2_2") (pintype "passive"))
      (node (ref "X4") (pin "2") (pinfunction "2_2") (pintype "passive"))
      (node (ref "X5") (pin "4") (pinfunction "4_4") (pintype "passive"))
      (node (ref "X6") (pin "2") (pinfunction "2_2") (pintype "passive"))
      (node (ref "X7") (pin "4") (pinfunction "4_4") (pintype "passive"))
      (node (ref "X8") (pin "8") (pinfunction "8_8") (pintype "passive"))
    )
    (net (code "38") (name "Net-(BT1-+)") (class "Default")
      (node (ref "BT1") (pin "1") (pinfunction "+_1") (pintype "power_in"))
      (node (ref "X2") (pin "21") (pinfunction "VBAT_21") (pintype "passive"))
    )
    (net (code "39") (name "Net-(D1-Pad1)") (class "Default")
      (node (ref "D1") (pin "1") (pinfunction "1_1") (pintype "passive"))
      (node (ref "R1") (pin "1") (pinfunction "1_1") (pintype "passive"))
    )
    (net (code "40") (name "Net-(D2-Pad1)") (class "Default")
      (node (ref "D2") (pin "1") (pinfunction "1_1") (pintype "passive"))
      (node (ref "R2") (pin "1") (pinfunction "1_1") (pintype "passive"))
    )
    (net (code "41") (name "Net-(D4-Pad1)") (class "Default")
      (node (ref "D4") (pin "1") (pinfunction "1_1") (pintype "passive"))
      (node (ref "R4") (pin "1") (pinfunction "1_1") (pintype "passive"))
    )
    (net (code "42") (name "Net-(D5-Pad1)") (class "Default")
      (node (ref "D5") (pin "1") (pinfunction "1_1") (pintype "passive"))
      (node (ref "R5") (pin "1") (pinfunction "1_1") (pintype "passive"))
    )
    (net (code "43") (name "Net-(D7-Pad1)") (class "Default")
      (node (ref "D7") (pin "1") (pinfunction "1_1") (pintype "passive"))
      (node (ref "R23") (pin "1") (pinfunction "1_1") (pintype "passive"))
    )
    (net (code "44") (name "Net-(U2-C1+)") (class "Default")
      (node (ref "C9") (pin "1") (pinfunction "1_1") (pintype "passive"))
      (node (ref "U2") (pin "1") (pinfunction "C1+_1") (pintype "passive"))
    )
    (net (code "45") (name "Net-(U2-C1-)") (class "Default")
      (node (ref "C9") (pin "2") (pinfunction "2_2") (pintype "passive"))
      (node (ref "U2") (pin "3") (pinfunction "C1-_3") (pintype "passive"))
    )
    (net (code "46") (name "Net-(U2-C2+)") (class "Default")
      (node (ref "C10") (pin "1") (pinfunction "1_1") (pintype "passive"))
      (node (ref "U2") (pin "4") (pinfunction "C2+_4") (pintype "passive"))
    )
    (net (code "47") (name "Net-(U2-C2-)") (class "Default")
      (node (ref "C10") (pin "2") (pinfunction "2_2") (pintype "passive"))
      (node (ref "U2") (pin "5") (pinfunction "C2-_5") (pintype "passive"))
    )
    (net (code "48") (name "Net-(U2-V+)") (class "Default")
      (node (ref "C2") (pin "1") (pinfunction "1_1") (pintype "passive"))
      (node (ref "U2") (pin "2") (pinfunction "V+_2") (pintype "power_in"))
    )
    (net (code "49") (name "Net-(U2-V-)") (class "Default")
      (node (ref "C3") (pin "2") (pinfunction "2_2") (pintype "passive"))
      (node (ref "U2") (pin "6") (pinfunction "V-_6") (pintype "power_in"))
    )
    (net (code "50") (name "Net-(U3-BOOT)") (class "Default")
      (node (ref "C11") (pin "1") (pinfunction "1_1") (pintype "passive"))
      (node (ref "U3") (pin "1") (pinfunction "BOOT_1") (pintype "passive"))
    )
    (net (code "51") (name "Net-(U3-EN)") (class "Default")
      (node (ref "R7") (pin "1") (pinfunction "1_1") (pintype "passive"))
      (node (ref "U3") (pin "5") (pinfunction "EN_5") (pintype "passive"))
    )
    (net (code "52") (name "Net-(U3-RT{slash}SYNC)") (class "Default")
      (node (ref "R8") (pin "2") (pinfunction "2_2") (pintype "passive"))
      (node (ref "U3") (pin "3") (pinfunction "RT/SYNC_3") (pintype "passive"))
    )
    (net (code "53") (name "Net-(U3-SW)") (class "Default")
      (node (ref "C11") (pin "2") (pinfunction "2_2") (pintype "passive"))
      (node (ref "D6") (pin "2") (pinfunction "2_2") (pintype "passive"))
      (node (ref "L1") (pin "2") (pinfunction "2_2") (pintype "passive"))
      (node (ref "U3") (pin "8") (pinfunction "SW_8") (pintype "passive"))
    )
    (net (code "54") (name "Net-(U3-VIN)") (class "Default")
      (node (ref "C5") (pin "1") (pinfunction "1_1") (pintype "passive"))
      (node (ref "C6") (pin "2") (pinfunction "2_2") (pintype "passive"))
      (node (ref "C7") (pin "2") (pinfunction "2_2") (pintype "passive"))
      (node (ref "C8") (pin "2") (pinfunction "2_2") (pintype "passive"))
      (node (ref "D3") (pin "2") (pinfunction "2_2") (pintype "passive"))
      (node (ref "F1") (pin "2") (pintype "passive"))
      (node (ref "R7") (pin "2") (pinfunction "2_2") (pintype "passive"))
      (node (ref "U3") (pin "7") (pinfunction "VIN_7") (pintype "passive"))
    )
    (net (code "55") (name "Net-(U4-1A)") (class "Default")
      (node (ref "C12") (pin "2") (pinfunction "2_2") (pintype "passive"))
      (node (ref "R10") (pin "1") (pinfunction "1_1") (pintype "passive"))
      (node (ref "U4") (pin "1") (pinfunction "1A_1") (pintype "passive"))
    )
    (net (code "56") (name "Net-(U4-2A)") (class "Default")
      (node (ref "C13") (pin "2") (pinfunction "2_2") (pintype "passive"))
      (node (ref "R11") (pin "1") (pinfunction "1_1") (pintype "passive"))
      (node (ref "U4") (pin "3") (pinfunction "2A_3") (pintype "passive"))
    )
    (net (code "57") (name "Net-(U4-3A)") (class "Default")
      (node (ref "C14") (pin "2") (pinfunction "2_2") (pintype "passive"))
      (node (ref "R12") (pin "1") (pinfunction "1_1") (pintype "passive"))
      (node (ref "U4") (pin "5") (pinfunction "3A_5") (pintype "passive"))
    )
    (net (code "58") (name "Net-(U4-4A)") (class "Default")
      (node (ref "C17") (pin "2") (pinfunction "2_2") (pintype "passive"))
      (node (ref "R20") (pin "1") (pinfunction "1_1") (pintype "passive"))
      (node (ref "U4") (pin "9") (pinfunction "4A_9") (pintype "passive"))
    )
    (net (code "59") (name "Net-(U4-5A)") (class "Default")
      (node (ref "C18") (pin "2") (pinfunction "2_2") (pintype "passive"))
      (node (ref "R21") (pin "1") (pinfunction "1_1") (pintype "passive"))
      (node (ref "U4") (pin "11") (pinfunction "5A_11") (pintype "passive"))
    )
    (net (code "60") (name "Net-(U4-6A)") (class "Default")
      (node (ref "C19") (pin "2") (pinfunction "2_2") (pintype "passive"))
      (node (ref "R22") (pin "1") (pinfunction "1_1") (pintype "passive"))
      (node (ref "U4") (pin "13") (pinfunction "6A_13") (pintype "passive"))
    )
    (net (code "61") (name "Net-(X2-PB0)") (class "Default")
      (node (ref "R25") (pin "2") (pinfunction "2_2") (pintype "passive"))
      (node (ref "X2") (pin "34") (pinfunction "PB0_34") (pintype "passive"))
    )
    (net (code "62") (name "Net-(X2-PB1)") (class "Default")
      (node (ref "R24") (pin "2") (pinfunction "2_2") (pintype "passive"))
      (node (ref "X2") (pin "35") (pinfunction "PB1_35") (pintype "passive"))
    )
    (net (code "63") (name "Net-(X2-PB3)") (class "Default")
      (node (ref "R16") (pin "1") (pinfunction "1_1") (pintype "passive"))
      (node (ref "X2") (pin "11") (pinfunction "PB3_11") (pintype "passive"))
    )
    (net (code "64") (name "Net-(X2-PB4)") (class "Default")
      (node (ref "R17") (pin "1") (pinfunction "1_1") (pintype "passive"))
      (node (ref "X2") (pin "12") (pinfunction "PB4_12") (pintype "passive"))
    )
    (net (code "65") (name "Net-(X2-PB5)") (class "Default")
      (node (ref "R18") (pin "1") (pinfunction "1_1") (pintype "passive"))
      (node (ref "X2") (pin "13") (pinfunction "PB5_13") (pintype "passive"))
    )
    (net (code "66") (name "Net-(X2-PB8)") (class "Default")
      (node (ref "R19") (pin "1") (pinfunction "1_1") (pintype "passive"))
      (node (ref "X2") (pin "16") (pinfunction "PB8_16") (pintype "passive"))
    )
    (net (code "67") (name "unconnected-(U2-DIN2-Pad10)") (class "Default")
      (node (ref "U2") (pin "10") (pinfunction "DIN2_10") (pintype "passive"))
    )
    (net (code "68") (name "unconnected-(U2-DOUT2-Pad7)") (class "Default")
      (node (ref "U2") (pin "7") (pinfunction "DOUT2_7") (pintype "passive"))
    )
    (net (code "69") (name "unconnected-(U2-RIN2-Pad8)") (class "Default")
      (node (ref "U2") (pin "8") (pinfunction "RIN2_8") (pintype "passive"))
    )
    (net (code "70") (name "unconnected-(U2-ROUT2-Pad9)") (class "Default")
      (node (ref "U2") (pin "9") (pinfunction "ROUT2_9") (pintype "passive"))
    )
    (net (code "71") (name "unconnected-(U3-NC-Pad2)") (class "Default")
      (node (ref "U3") (pin "2") (pinfunction "NC_2") (pintype "passive"))
    )
    (net (code "72") (name "unconnected-(X1-Pad3)") (class "Default")
      (node (ref "X1") (pin "3") (pinfunction "3_3") (pintype "passive"))
    )
    (net (code "73") (name "unconnected-(X1-Pad6)") (class "Default")
      (node (ref "X1") (pin "6") (pinfunction "6_6") (pintype "passive"))
    )
    (net (code "74") (name "unconnected-(X2-3V3-Pad20)") (class "Default")
      (node (ref "X2") (pin "20") (pinfunction "3V3_20") (pintype "passive"))
    )
    (net (code "75") (name "unconnected-(X2-3V3-Pad38)") (class "Default")
      (node (ref "X2") (pin "38") (pinfunction "3V3_38") (pintype "passive"))
    )
    (net (code "76") (name "unconnected-(X2-PB2-Pad36)") (class "Default")
      (node (ref "X2") (pin "36") (pinfunction "PB2_36") (pintype "passive"))
    )
    (net (code "77") (name "unconnected-(X2-PB9-Pad17)") (class "Default")
      (node (ref "X2") (pin "17") (pinfunction "PB9_17") (pintype "passive"))
    )
    (net (code "78") (name "unconnected-(X2-PB10-Pad37)") (class "Default")
      (node (ref "X2") (pin "37") (pinfunction "PB10_37") (pintype "passive"))
    )
    (net (code "79") (name "unconnected-(X2-PC13-Pad22)") (class "Default")
      (node (ref "X2") (pin "22") (pinfunction "PC13_22") (pintype "passive"))
    )
    (net (code "80") (name "unconnected-(X2-PC14-Pad23)") (class "Default")
      (node (ref "X2") (pin "23") (pinfunction "PC14_23") (pintype "passive"))
    )
    (net (code "81") (name "unconnected-(X2-PC15-Pad24)") (class "Default")
      (node (ref "X2") (pin "24") (pinfunction "PC15_24") (pintype "passive"))
    )
    (net (code "82") (name "unconnected-(X2-RST-Pad25)") (class "Default")
      (node (ref "X2") (pin "25") (pinfunction "RST_25") (pintype "passive"))
    )
  )
)
